# rpm-meter.net
KiCad netlist of a schematic drawn in EAGLE
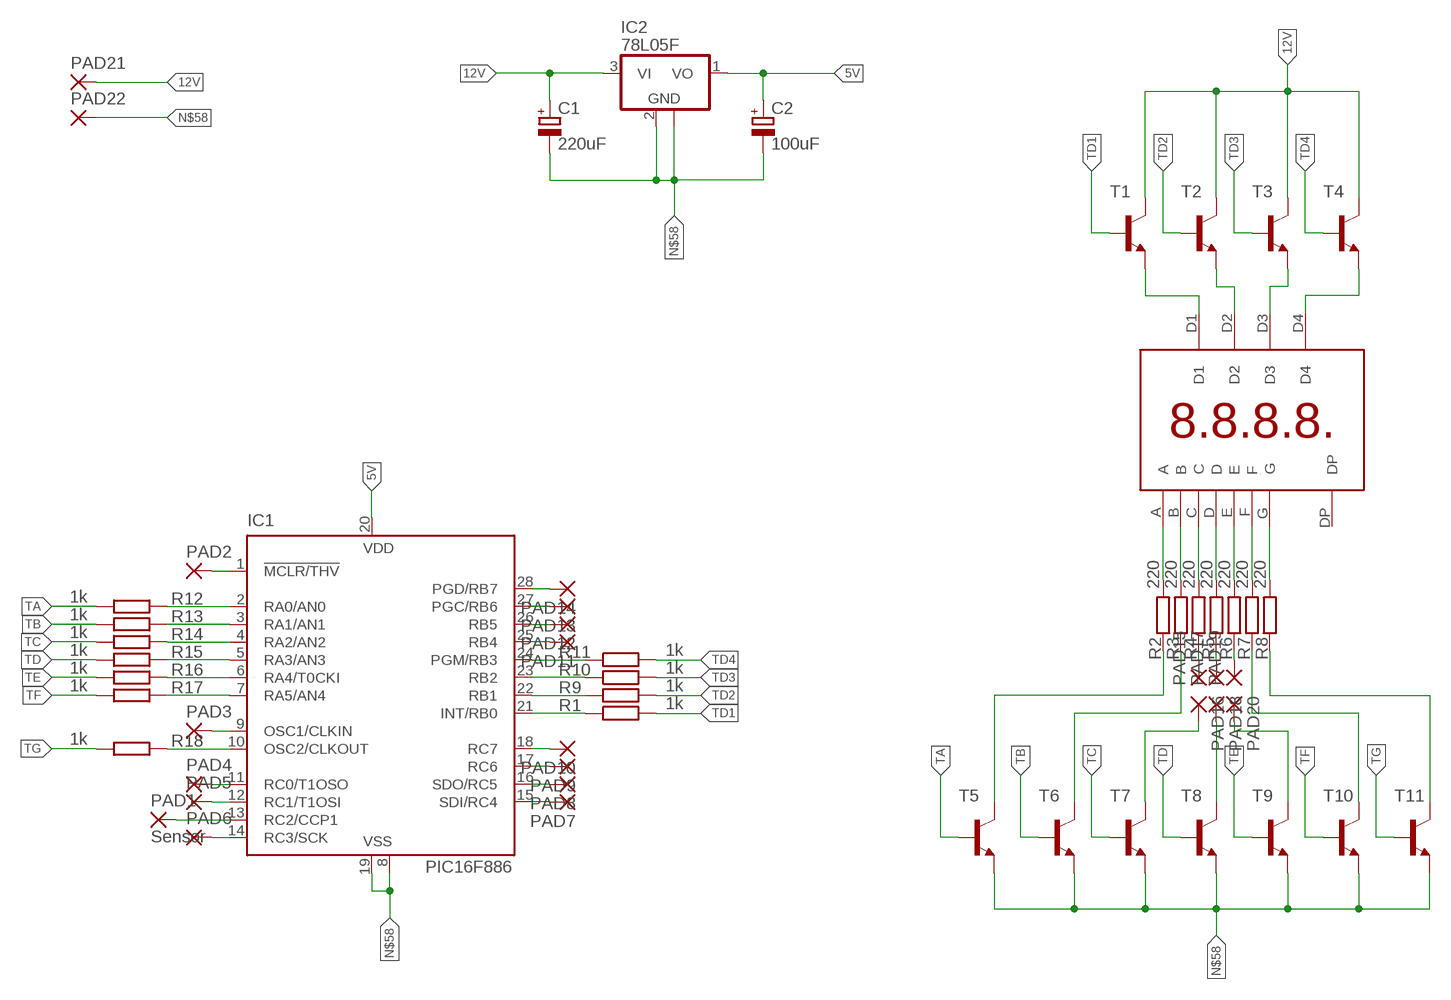
[diagram p0: schematic, sheet 1]

(export (version "E")
  (design (tool "Eeschema 10.0.6"))
  (components
    (comp (ref "C1")
      (value "220uF")
      (footprint "eagle-import:E5-6")
      (libsource (lib "eagle-import") (part "CPOL-EUE5-6"))
    )
    (comp (ref "C2")
      (value "100uF")
      (footprint "eagle-import:E5-5")
      (libsource (lib "eagle-import") (part "CPOL-EUE5-5"))
    )
    (comp (ref "IC1")
      (value "PIC16F886")
      (footprint "eagle-import:DIL28-3")
      (libsource (lib "eagle-import") (part "PIC16873P"))
    )
    (comp (ref "IC2")
      (value "78L05F")
      (footprint "eagle-import:SOT89")
      (libsource (lib "eagle-import") (part "78LF05"))
    )
    (comp (ref "PAD1")
      (value "Sensor")
      (footprint "eagle-import:SMD2,54-5,08")
      (libsource (lib "eagle-import") (part "SMD5"))
    )
    (comp (ref "PAD2")
      (value "SMD2")
      (footprint "eagle-import:SMD1,27-2,54")
      (libsource (lib "eagle-import") (part "SMD2"))
    )
    (comp (ref "PAD3")
      (value "SMD2")
      (footprint "eagle-import:SMD1,27-2,54")
      (libsource (lib "eagle-import") (part "SMD2"))
    )
    (comp (ref "PAD4")
      (value "SMD2")
      (footprint "eagle-import:SMD1,27-2,54")
      (libsource (lib "eagle-import") (part "SMD2"))
    )
    (comp (ref "PAD5")
      (value "SMD2")
      (footprint "eagle-import:SMD1,27-2,54")
      (libsource (lib "eagle-import") (part "SMD2"))
    )
    (comp (ref "PAD6")
      (value "SMD2")
      (footprint "eagle-import:SMD1,27-2,54")
      (libsource (lib "eagle-import") (part "SMD2"))
    )
    (comp (ref "PAD7")
      (value "SMD2")
      (footprint "eagle-import:SMD1,27-2,54")
      (libsource (lib "eagle-import") (part "SMD2"))
    )
    (comp (ref "PAD8")
      (value "SMD2")
      (footprint "eagle-import:SMD1,27-2,54")
      (libsource (lib "eagle-import") (part "SMD2"))
    )
    (comp (ref "PAD9")
      (value "SMD2")
      (footprint "eagle-import:SMD1,27-2,54")
      (libsource (lib "eagle-import") (part "SMD2"))
    )
    (comp (ref "PAD10")
      (value "SMD2")
      (footprint "eagle-import:SMD1,27-2,54")
      (libsource (lib "eagle-import") (part "SMD2"))
    )
    (comp (ref "PAD11")
      (value "SMD2")
      (footprint "eagle-import:SMD1,27-2,54")
      (libsource (lib "eagle-import") (part "SMD2"))
    )
    (comp (ref "PAD12")
      (value "SMD2")
      (footprint "eagle-import:SMD1,27-2,54")
      (libsource (lib "eagle-import") (part "SMD2"))
    )
    (comp (ref "PAD13")
      (value "SMD2")
      (footprint "eagle-import:SMD1,27-2,54")
      (libsource (lib "eagle-import") (part "SMD2"))
    )
    (comp (ref "PAD14")
      (value "SMD2")
      (footprint "eagle-import:SMD1,27-2,54")
      (libsource (lib "eagle-import") (part "SMD2"))
    )
    (comp (ref "PAD15")
      (value "2,54/0,8")
      (footprint "eagle-import:2,54_0,8")
      (libsource (lib "eagle-import") (part "2,54/0,8"))
    )
    (comp (ref "PAD16")
      (value "2,54/0,8")
      (footprint "eagle-import:2,54_0,8")
      (libsource (lib "eagle-import") (part "2,54/0,8"))
    )
    (comp (ref "PAD17")
      (value "2,54/0,8")
      (footprint "eagle-import:2,54_0,8")
      (libsource (lib "eagle-import") (part "2,54/0,8"))
    )
    (comp (ref "PAD18")
      (value "2,54/0,8")
      (footprint "eagle-import:2,54_0,8")
      (libsource (lib "eagle-import") (part "2,54/0,8"))
    )
    (comp (ref "PAD19")
      (value "2,54/0,8")
      (footprint "eagle-import:2,54_0,8")
      (libsource (lib "eagle-import") (part "2,54/0,8"))
    )
    (comp (ref "PAD20")
      (value "2,54/0,8")
      (footprint "eagle-import:2,54_0,8")
      (libsource (lib "eagle-import") (part "2,54/0,8"))
    )
    (comp (ref "PAD21")
      (value "SMD5")
      (footprint "eagle-import:SMD2,54-5,08")
      (libsource (lib "eagle-import") (part "SMD5"))
    )
    (comp (ref "PAD22")
      (value "SMD5")
      (footprint "eagle-import:SMD2,54-5,08")
      (libsource (lib "eagle-import") (part "SMD5"))
    )
    (comp (ref "R1")
      (value "1k")
      (footprint "eagle-import:M0805")
      (libsource (lib "eagle-import") (part "R-EU_M0805"))
    )
    (comp (ref "R2")
      (value "220")
      (footprint "eagle-import:M0805")
      (libsource (lib "eagle-import") (part "R-EU_M0805"))
    )
    (comp (ref "R3")
      (value "220")
      (footprint "eagle-import:M0805")
      (libsource (lib "eagle-import") (part "R-EU_M0805"))
    )
    (comp (ref "R4")
      (value "220")
      (footprint "eagle-import:M0805")
      (libsource (lib "eagle-import") (part "R-EU_M0805"))
    )
    (comp (ref "R5")
      (value "220")
      (footprint "eagle-import:M0805")
      (libsource (lib "eagle-import") (part "R-EU_M0805"))
    )
    (comp (ref "R6")
      (value "220")
      (footprint "eagle-import:M0805")
      (libsource (lib "eagle-import") (part "R-EU_M0805"))
    )
    (comp (ref "R7")
      (value "220")
      (footprint "eagle-import:M0805")
      (libsource (lib "eagle-import") (part "R-EU_M0805"))
    )
    (comp (ref "R8")
      (value "220")
      (footprint "eagle-import:M0805")
      (libsource (lib "eagle-import") (part "R-EU_M0805"))
    )
    (comp (ref "R9")
      (value "1k")
      (footprint "eagle-import:M0805")
      (libsource (lib "eagle-import") (part "R-EU_M0805"))
    )
    (comp (ref "R10")
      (value "1k")
      (footprint "eagle-import:M0805")
      (libsource (lib "eagle-import") (part "R-EU_M0805"))
    )
    (comp (ref "R11")
      (value "1k")
      (footprint "eagle-import:M0805")
      (libsource (lib "eagle-import") (part "R-EU_M0805"))
    )
    (comp (ref "R12")
      (value "1k")
      (footprint "eagle-import:M0805")
      (libsource (lib "eagle-import") (part "R-EU_M0805"))
    )
    (comp (ref "R13")
      (value "1k")
      (footprint "eagle-import:M0805")
      (libsource (lib "eagle-import") (part "R-EU_M0805"))
    )
    (comp (ref "R14")
      (value "1k")
      (footprint "eagle-import:M0805")
      (libsource (lib "eagle-import") (part "R-EU_M0805"))
    )
    (comp (ref "R15")
      (value "1k")
      (footprint "eagle-import:M0805")
      (libsource (lib "eagle-import") (part "R-EU_M0805"))
    )
    (comp (ref "R16")
      (value "1k")
      (footprint "eagle-import:M0805")
      (libsource (lib "eagle-import") (part "R-EU_M0805"))
    )
    (comp (ref "R17")
      (value "1k")
      (footprint "eagle-import:M0805")
      (libsource (lib "eagle-import") (part "R-EU_M0805"))
    )
    (comp (ref "R18")
      (value "1k")
      (footprint "eagle-import:M0805")
      (libsource (lib "eagle-import") (part "R-EU_M0805"))
    )
    (comp (ref "T1")
      (value "-NPN-SOT23-EBC")
      (footprint "eagle-import:SOT23-EBC")
      (libsource (lib "eagle-import") (part "-NPN-SOT23-EBC"))
    )
    (comp (ref "T2")
      (value "-NPN-SOT23-EBC")
      (footprint "eagle-import:SOT23-EBC")
      (libsource (lib "eagle-import") (part "-NPN-SOT23-EBC"))
    )
    (comp (ref "T3")
      (value "-NPN-SOT23-EBC")
      (footprint "eagle-import:SOT23-EBC")
      (libsource (lib "eagle-import") (part "-NPN-SOT23-EBC"))
    )
    (comp (ref "T4")
      (value "-NPN-SOT23-EBC")
      (footprint "eagle-import:SOT23-EBC")
      (libsource (lib "eagle-import") (part "-NPN-SOT23-EBC"))
    )
    (comp (ref "T5")
      (value "-NPN-SOT23-EBC")
      (footprint "eagle-import:SOT23-EBC")
      (libsource (lib "eagle-import") (part "-NPN-SOT23-EBC"))
    )
    (comp (ref "T6")
      (value "-NPN-SOT23-EBC")
      (footprint "eagle-import:SOT23-EBC")
      (libsource (lib "eagle-import") (part "-NPN-SOT23-EBC"))
    )
    (comp (ref "T7")
      (value "-NPN-SOT23-EBC")
      (footprint "eagle-import:SOT23-EBC")
      (libsource (lib "eagle-import") (part "-NPN-SOT23-EBC"))
    )
    (comp (ref "T8")
      (value "-NPN-SOT23-EBC")
      (footprint "eagle-import:SOT23-EBC")
      (libsource (lib "eagle-import") (part "-NPN-SOT23-EBC"))
    )
    (comp (ref "T9")
      (value "-NPN-SOT23-EBC")
      (footprint "eagle-import:SOT23-EBC")
      (libsource (lib "eagle-import") (part "-NPN-SOT23-EBC"))
    )
    (comp (ref "T10")
      (value "-NPN-SOT23-EBC")
      (footprint "eagle-import:SOT23-EBC")
      (libsource (lib "eagle-import") (part "-NPN-SOT23-EBC"))
    )
    (comp (ref "T11")
      (value "-NPN-SOT23-EBC")
      (footprint "eagle-import:SOT23-EBC")
      (libsource (lib "eagle-import") (part "-NPN-SOT23-EBC"))
    )
    (comp (ref "U$1")
      (value "4X7SEG-CA")
      (footprint "eagle-import:4X7SEG-CA")
      (libsource (lib "eagle-import") (part "4X7SEG-CA"))
    )
  )
  (nets
    (net (code "1") (name "5V") (class "Default")
      (node (ref "C2") (pin "+") (pinfunction "+_+") (pintype "passive"))
      (node (ref "IC1") (pin "20") (pinfunction "VDD_20") (pintype "power_in"))
      (node (ref "IC2") (pin "1") (pinfunction "VO_1") (pintype "passive"))
    )
    (net (code "2") (name "12V") (class "Default")
      (node (ref "C1") (pin "+") (pinfunction "+_+") (pintype "passive"))
      (node (ref "IC2") (pin "3") (pinfunction "VI_3") (pintype "input"))
      (node (ref "PAD21") (pin "1") (pinfunction "P_1") (pintype "passive"))
      (node (ref "T1") (pin "C") (pinfunction "C_C") (pintype "passive"))
      (node (ref "T2") (pin "C") (pinfunction "C_C") (pintype "passive"))
      (node (ref "T3") (pin "C") (pinfunction "C_C") (pintype "passive"))
      (node (ref "T4") (pin "C") (pinfunction "C_C") (pintype "passive"))
    )
    (net (code "3") (name "N$58") (class "Default")
      (node (ref "C1") (pin "-") (pinfunction "-_-") (pintype "passive"))
      (node (ref "C2") (pin "-") (pinfunction "-_-") (pintype "passive"))
      (node (ref "IC1") (pin "19") (pinfunction "VSS_19") (pintype "power_in"))
      (node (ref "IC1") (pin "8") (pinfunction "VSS_8") (pintype "power_in"))
      (node (ref "IC2") (pin "2") (pinfunction "GND_2") (pintype "passive"))
      (node (ref "IC2") (pin "2@1") (pinfunction "GND_2@1") (pintype "passive"))
      (node (ref "PAD22") (pin "1") (pinfunction "P_1") (pintype "passive"))
      (node (ref "T10") (pin "E") (pinfunction "E_E") (pintype "passive"))
      (node (ref "T11") (pin "E") (pinfunction "E_E") (pintype "passive"))
      (node (ref "T5") (pin "E") (pinfunction "E_E") (pintype "passive"))
      (node (ref "T6") (pin "E") (pinfunction "E_E") (pintype "passive"))
      (node (ref "T7") (pin "E") (pinfunction "E_E") (pintype "passive"))
      (node (ref "T8") (pin "E") (pinfunction "E_E") (pintype "passive"))
      (node (ref "T9") (pin "E") (pinfunction "E_E") (pintype "passive"))
    )
    (net (code "4") (name "Net-(IC1-INT{slash}RB0)") (class "Default")
      (node (ref "IC1") (pin "21") (pinfunction "INT/RB0_21") (pintype "bidirectional"))
      (node (ref "R1") (pin "1") (pinfunction "1_1") (pintype "passive"))
    )
    (net (code "5") (name "Net-(IC1-OSC1{slash}CLKIN)") (class "Default")
      (node (ref "IC1") (pin "9") (pinfunction "OSC1/CLKIN_9") (pintype "input"))
      (node (ref "PAD3") (pin "1") (pinfunction "P_1") (pintype "passive"))
    )
    (net (code "6") (name "Net-(IC1-OSC2{slash}CLKOUT)") (class "Default")
      (node (ref "IC1") (pin "10") (pinfunction "OSC2/CLKOUT_10") (pintype "output"))
      (node (ref "R18") (pin "1") (pinfunction "1_1") (pintype "passive"))
    )
    (net (code "7") (name "Net-(IC1-PGC{slash}RB6)") (class "Default")
      (node (ref "IC1") (pin "27") (pinfunction "PGC/RB6_27") (pintype "bidirectional"))
      (node (ref "PAD13") (pin "1") (pinfunction "P_1") (pintype "passive"))
    )
    (net (code "8") (name "Net-(IC1-PGD{slash}RB7)") (class "Default")
      (node (ref "IC1") (pin "28") (pinfunction "PGD/RB7_28") (pintype "bidirectional"))
      (node (ref "PAD14") (pin "1") (pinfunction "P_1") (pintype "passive"))
    )
    (net (code "9") (name "Net-(IC1-PGM{slash}RB3)") (class "Default")
      (node (ref "IC1") (pin "24") (pinfunction "PGM/RB3_24") (pintype "bidirectional"))
      (node (ref "R11") (pin "1") (pinfunction "1_1") (pintype "passive"))
    )
    (net (code "10") (name "Net-(IC1-RA0{slash}AN0)") (class "Default")
      (node (ref "IC1") (pin "2") (pinfunction "RA0/AN0_2") (pintype "bidirectional"))
      (node (ref "R12") (pin "1") (pinfunction "1_1") (pintype "passive"))
    )
    (net (code "11") (name "Net-(IC1-RA1{slash}AN1)") (class "Default")
      (node (ref "IC1") (pin "3") (pinfunction "RA1/AN1_3") (pintype "bidirectional"))
      (node (ref "R13") (pin "1") (pinfunction "1_1") (pintype "passive"))
    )
    (net (code "12") (name "Net-(IC1-RA2{slash}AN2)") (class "Default")
      (node (ref "IC1") (pin "4") (pinfunction "RA2/AN2_4") (pintype "bidirectional"))
      (node (ref "R14") (pin "1") (pinfunction "1_1") (pintype "passive"))
    )
    (net (code "13") (name "Net-(IC1-RA3{slash}AN3)") (class "Default")
      (node (ref "IC1") (pin "5") (pinfunction "RA3/AN3_5") (pintype "bidirectional"))
      (node (ref "R15") (pin "1") (pinfunction "1_1") (pintype "passive"))
    )
    (net (code "14") (name "Net-(IC1-RA4{slash}T0CKI)") (class "Default")
      (node (ref "IC1") (pin "6") (pinfunction "RA4/T0CKI_6") (pintype "bidirectional"))
      (node (ref "R16") (pin "1") (pinfunction "1_1") (pintype "passive"))
    )
    (net (code "15") (name "Net-(IC1-RA5{slash}AN4)") (class "Default")
      (node (ref "IC1") (pin "7") (pinfunction "RA5/AN4_7") (pintype "bidirectional"))
      (node (ref "R17") (pin "1") (pinfunction "1_1") (pintype "passive"))
    )
    (net (code "16") (name "Net-(IC1-RB1)") (class "Default")
      (node (ref "IC1") (pin "22") (pinfunction "RB1_22") (pintype "bidirectional"))
      (node (ref "R9") (pin "1") (pinfunction "1_1") (pintype "passive"))
    )
    (net (code "17") (name "Net-(IC1-RB2)") (class "Default")
      (node (ref "IC1") (pin "23") (pinfunction "RB2_23") (pintype "bidirectional"))
      (node (ref "R10") (pin "1") (pinfunction "1_1") (pintype "passive"))
    )
    (net (code "18") (name "Net-(IC1-RB4)") (class "Default")
      (node (ref "IC1") (pin "25") (pinfunction "RB4_25") (pintype "bidirectional"))
      (node (ref "PAD11") (pin "1") (pinfunction "P_1") (pintype "passive"))
    )
    (net (code "19") (name "Net-(IC1-RB5)") (class "Default")
      (node (ref "IC1") (pin "26") (pinfunction "RB5_26") (pintype "bidirectional"))
      (node (ref "PAD12") (pin "1") (pinfunction "P_1") (pintype "passive"))
    )
    (net (code "20") (name "Net-(IC1-RC0{slash}T1OSO)") (class "Default")
      (node (ref "IC1") (pin "11") (pinfunction "RC0/T1OSO_11") (pintype "bidirectional"))
      (node (ref "PAD4") (pin "1") (pinfunction "P_1") (pintype "passive"))
    )
    (net (code "21") (name "Net-(IC1-RC1{slash}T1OSI)") (class "Default")
      (node (ref "IC1") (pin "12") (pinfunction "RC1/T1OSI_12") (pintype "bidirectional"))
      (node (ref "PAD5") (pin "1") (pinfunction "P_1") (pintype "passive"))
    )
    (net (code "22") (name "Net-(IC1-RC2{slash}CCP1)") (class "Default")
      (node (ref "IC1") (pin "13") (pinfunction "RC2/CCP1_13") (pintype "bidirectional"))
      (node (ref "PAD1") (pin "1") (pinfunction "P_1") (pintype "passive"))
    )
    (net (code "23") (name "Net-(IC1-RC3{slash}SCK)") (class "Default")
      (node (ref "IC1") (pin "14") (pinfunction "RC3/SCK_14") (pintype "bidirectional"))
      (node (ref "PAD6") (pin "1") (pinfunction "P_1") (pintype "passive"))
    )
    (net (code "24") (name "Net-(IC1-RC6)") (class "Default")
      (node (ref "IC1") (pin "17") (pinfunction "RC6_17") (pintype "bidirectional"))
      (node (ref "PAD9") (pin "1") (pinfunction "P_1") (pintype "passive"))
    )
    (net (code "25") (name "Net-(IC1-RC7)") (class "Default")
      (node (ref "IC1") (pin "18") (pinfunction "RC7_18") (pintype "bidirectional"))
      (node (ref "PAD10") (pin "1") (pinfunction "P_1") (pintype "passive"))
    )
    (net (code "26") (name "Net-(IC1-SDI{slash}RC4)") (class "Default")
      (node (ref "IC1") (pin "15") (pinfunction "SDI/RC4_15") (pintype "bidirectional"))
      (node (ref "PAD7") (pin "1") (pinfunction "P_1") (pintype "passive"))
    )
    (net (code "27") (name "Net-(IC1-SDO{slash}RC5)") (class "Default")
      (node (ref "IC1") (pin "16") (pinfunction "SDO/RC5_16") (pintype "bidirectional"))
      (node (ref "PAD8") (pin "1") (pinfunction "P_1") (pintype "passive"))
    )
    (net (code "28") (name "Net-(IC1-~{MCLR{slash}THV})") (class "Default")
      (node (ref "IC1") (pin "1") (pinfunction "~{MCLR/THV}_1") (pintype "input"))
      (node (ref "PAD2") (pin "1") (pinfunction "P_1") (pintype "passive"))
    )
    (net (code "29") (name "Net-(PAD15-P)") (class "Default")
      (node (ref "PAD15") (pin "1") (pinfunction "P_1") (pintype "passive"))
      (node (ref "R4") (pin "1") (pinfunction "1_1") (pintype "passive"))
    )
    (net (code "30") (name "Net-(PAD16-P)") (class "Default")
      (node (ref "PAD16") (pin "1") (pinfunction "P_1") (pintype "passive"))
      (node (ref "T7") (pin "C") (pinfunction "C_C") (pintype "passive"))
    )
    (net (code "31") (name "Net-(PAD17-P)") (class "Default")
      (node (ref "PAD17") (pin "1") (pinfunction "P_1") (pintype "passive"))
      (node (ref "R5") (pin "1") (pinfunction "1_1") (pintype "passive"))
    )
    (net (code "32") (name "Net-(PAD18-P)") (class "Default")
      (node (ref "PAD18") (pin "1") (pinfunction "P_1") (pintype "passive"))
      (node (ref "T8") (pin "C") (pinfunction "C_C") (pintype "passive"))
    )
    (net (code "33") (name "Net-(PAD19-P)") (class "Default")
      (node (ref "PAD19") (pin "1") (pinfunction "P_1") (pintype "passive"))
      (node (ref "R6") (pin "1") (pinfunction "1_1") (pintype "passive"))
    )
    (net (code "34") (name "Net-(PAD20-P)") (class "Default")
      (node (ref "PAD20") (pin "1") (pinfunction "P_1") (pintype "passive"))
      (node (ref "T9") (pin "C") (pinfunction "C_C") (pintype "passive"))
    )
    (net (code "35") (name "Net-(R2-Pad1)") (class "Default")
      (node (ref "R2") (pin "1") (pinfunction "1_1") (pintype "passive"))
      (node (ref "T5") (pin "C") (pinfunction "C_C") (pintype "passive"))
    )
    (net (code "36") (name "Net-(R2-Pad2)") (class "Default")
      (node (ref "R2") (pin "2") (pinfunction "2_2") (pintype "passive"))
      (node (ref "U$1") (pin "A") (pinfunction "A_A") (pintype "output"))
    )
    (net (code "37") (name "Net-(R3-Pad1)") (class "Default")
      (node (ref "R3") (pin "1") (pinfunction "1_1") (pintype "passive"))
      (node (ref "T6") (pin "C") (pinfunction "C_C") (pintype "passive"))
    )
    (net (code "38") (name "Net-(R3-Pad2)") (class "Default")
      (node (ref "R3") (pin "2") (pinfunction "2_2") (pintype "passive"))
      (node (ref "U$1") (pin "B") (pinfunction "B_B") (pintype "output"))
    )
    (net (code "39") (name "Net-(R4-Pad2)") (class "Default")
      (node (ref "R4") (pin "2") (pinfunction "2_2") (pintype "passive"))
      (node (ref "U$1") (pin "C") (pinfunction "C_C") (pintype "output"))
    )
    (net (code "40") (name "Net-(R5-Pad2)") (class "Default")
      (node (ref "R5") (pin "2") (pinfunction "2_2") (pintype "passive"))
      (node (ref "U$1") (pin "D") (pinfunction "D_D") (pintype "output"))
    )
    (net (code "41") (name "Net-(R6-Pad2)") (class "Default")
      (node (ref "R6") (pin "2") (pinfunction "2_2") (pintype "passive"))
      (node (ref "U$1") (pin "E") (pinfunction "E_E") (pintype "output"))
    )
    (net (code "42") (name "Net-(R7-Pad1)") (class "Default")
      (node (ref "R7") (pin "1") (pinfunction "1_1") (pintype "passive"))
      (node (ref "T10") (pin "C") (pinfunction "C_C") (pintype "passive"))
    )
    (net (code "43") (name "Net-(R7-Pad2)") (class "Default")
      (node (ref "R7") (pin "2") (pinfunction "2_2") (pintype "passive"))
      (node (ref "U$1") (pin "F") (pinfunction "F_F") (pintype "output"))
    )
    (net (code "44") (name "Net-(R8-Pad1)") (class "Default")
      (node (ref "R8") (pin "1") (pinfunction "1_1") (pintype "passive"))
      (node (ref "T11") (pin "C") (pinfunction "C_C") (pintype "passive"))
    )
    (net (code "45") (name "Net-(R8-Pad2)") (class "Default")
      (node (ref "R8") (pin "2") (pinfunction "2_2") (pintype "passive"))
      (node (ref "U$1") (pin "G") (pinfunction "G_G") (pintype "output"))
    )
    (net (code "46") (name "Net-(T1-PadE)") (class "Default")
      (node (ref "T1") (pin "E") (pinfunction "E_E") (pintype "passive"))
      (node (ref "U$1") (pin "D1") (pinfunction "D1_D1") (pintype "input"))
    )
    (net (code "47") (name "Net-(T2-PadE)") (class "Default")
      (node (ref "T2") (pin "E") (pinfunction "E_E") (pintype "passive"))
      (node (ref "U$1") (pin "D2") (pinfunction "D2_D2") (pintype "input"))
    )
    (net (code "48") (name "Net-(T3-PadE)") (class "Default")
      (node (ref "T3") (pin "E") (pinfunction "E_E") (pintype "passive"))
      (node (ref "U$1") (pin "D3") (pinfunction "D3_D3") (pintype "input"))
    )
    (net (code "49") (name "Net-(T4-PadE)") (class "Default")
      (node (ref "T4") (pin "E") (pinfunction "E_E") (pintype "passive"))
      (node (ref "U$1") (pin "D4") (pinfunction "D4_D4") (pintype "input"))
    )
    (net (code "50") (name "TA") (class "Default")
      (node (ref "R12") (pin "2") (pinfunction "2_2") (pintype "passive"))
      (node (ref "T5") (pin "B") (pinfunction "B_B") (pintype "passive"))
    )
    (net (code "51") (name "TB") (class "Default")
      (node (ref "R13") (pin "2") (pinfunction "2_2") (pintype "passive"))
      (node (ref "T6") (pin "B") (pinfunction "B_B") (pintype "passive"))
    )
    (net (code "52") (name "TC") (class "Default")
      (node (ref "R14") (pin "2") (pinfunction "2_2") (pintype "passive"))
      (node (ref "T7") (pin "B") (pinfunction "B_B") (pintype "passive"))
    )
    (net (code "53") (name "TD") (class "Default")
      (node (ref "R15") (pin "2") (pinfunction "2_2") (pintype "passive"))
      (node (ref "T8") (pin "B") (pinfunction "B_B") (pintype "passive"))
    )
    (net (code "54") (name "TD1") (class "Default")
      (node (ref "R1") (pin "2") (pinfunction "2_2") (pintype "passive"))
      (node (ref "T1") (pin "B") (pinfunction "B_B") (pintype "passive"))
    )
    (net (code "55") (name "TD2") (class "Default")
      (node (ref "R9") (pin "2") (pinfunction "2_2") (pintype "passive"))
      (node (ref "T2") (pin "B") (pinfunction "B_B") (pintype "passive"))
    )
    (net (code "56") (name "TD3") (class "Default")
      (node (ref "R10") (pin "2") (pinfunction "2_2") (pintype "passive"))
      (node (ref "T3") (pin "B") (pinfunction "B_B") (pintype "passive"))
    )
    (net (code "57") (name "TD4") (class "Default")
      (node (ref "R11") (pin "2") (pinfunction "2_2") (pintype "passive"))
      (node (ref "T4") (pin "B") (pinfunction "B_B") (pintype "passive"))
    )
    (net (code "58") (name "TE") (class "Default")
      (node (ref "R16") (pin "2") (pinfunction "2_2") (pintype "passive"))
      (node (ref "T9") (pin "B") (pinfunction "B_B") (pintype "passive"))
    )
    (net (code "59") (name "TF") (class "Default")
      (node (ref "R17") (pin "2") (pinfunction "2_2") (pintype "passive"))
      (node (ref "T10") (pin "B") (pinfunction "B_B") (pintype "passive"))
    )
    (net (code "60") (name "TG") (class "Default")
      (node (ref "R18") (pin "2") (pinfunction "2_2") (pintype "passive"))
      (node (ref "T11") (pin "B") (pinfunction "B_B") (pintype "passive"))
    )
    (net (code "61") (name "unconnected-(U$1-PadDP)") (class "Default")
      (node (ref "U$1") (pin "DP") (pinfunction "DP_DP") (pintype "output"))
    )
  )
)
